# CPU.net
KiCad netlist of a schematic drawn in Altium Designer
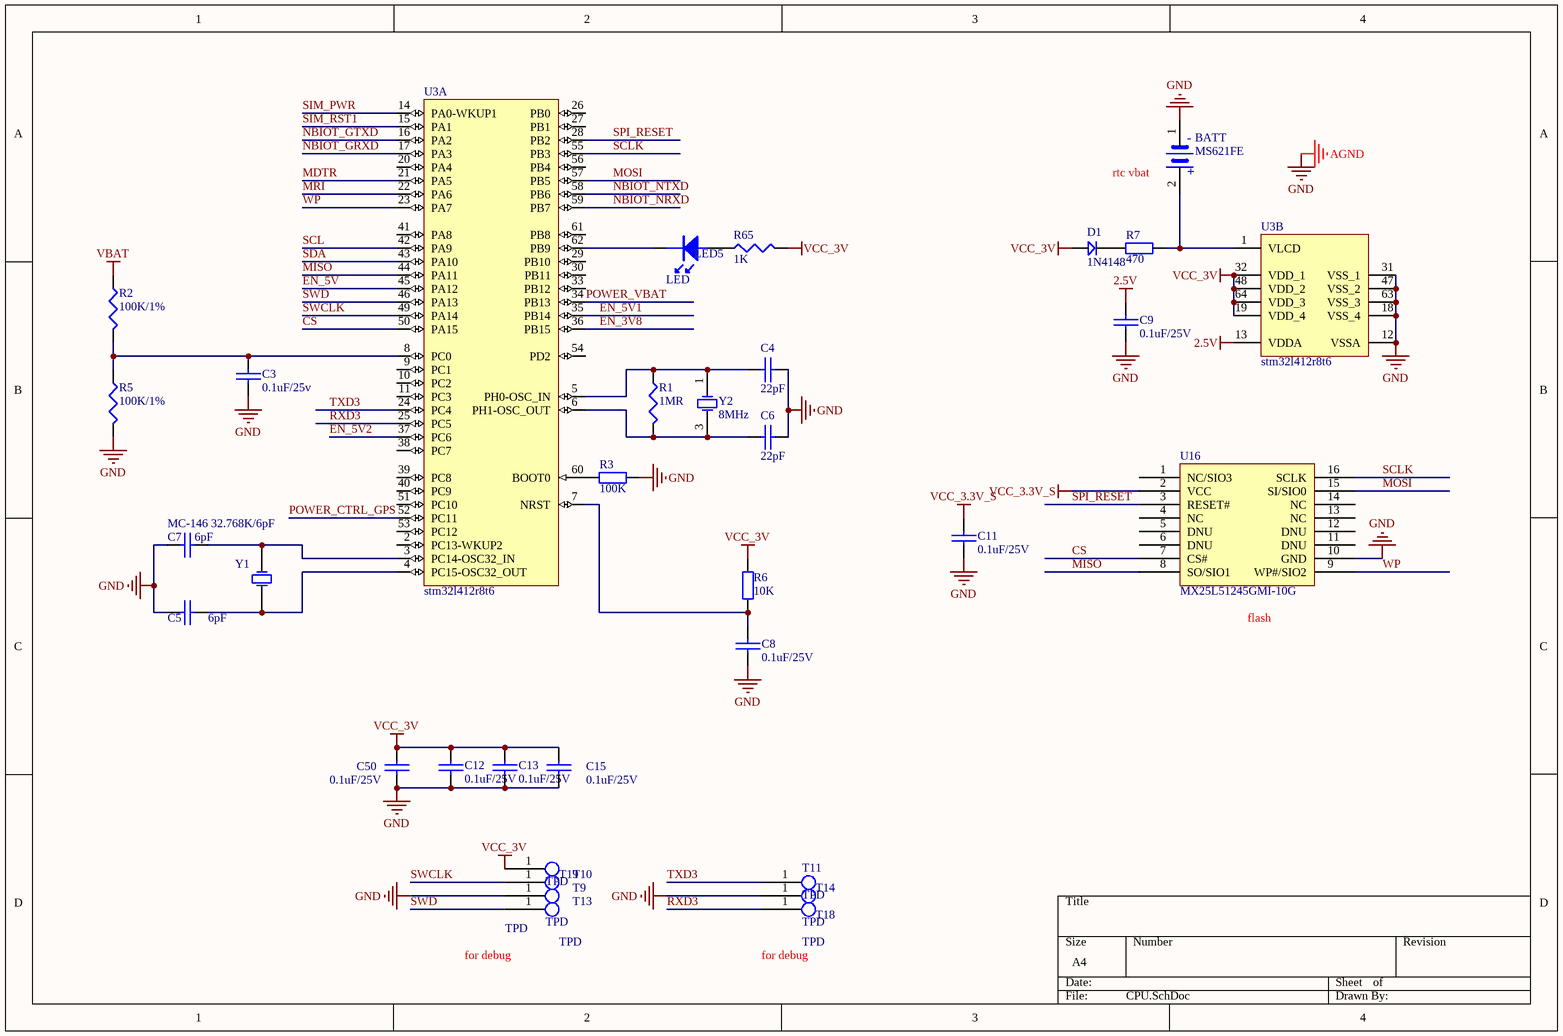
[diagram p0: CPU.SchDoc]

(export (version "E")
  (design (tool "Eeschema 10.0.6"))
  (components
    (comp (ref "BATT") (value "MS621FE") (footprint "MS621FE") (libsource (lib "Myself_1") (part "SBatery")))
    (comp (ref "C3")
      (value "0.1uF/25v")
      (footprint "0402c")
      (description "Capacitor")
      (libsource (lib "SM") (part "CAP"))
    )
    (comp (ref "C4")
      (value "22pF")
      (footprint "0402c")
      (description "Capacitor")
      (libsource (lib "SM") (part "CAP"))
    )
    (comp (ref "C5")
      (value "6pF")
      (footprint "0402c")
      (description "Capacitor")
      (libsource (lib "SM") (part "CAP"))
    )
    (comp (ref "C6")
      (value "22pF")
      (footprint "0402c")
      (description "Capacitor")
      (libsource (lib "SM") (part "CAP"))
    )
    (comp (ref "C7")
      (value "6pF")
      (footprint "0402c")
      (description "Capacitor")
      (libsource (lib "SM") (part "CAP"))
    )
    (comp (ref "C8")
      (value "0.1uF/25V")
      (footprint "0402C")
      (description "Capacitor")
      (libsource (lib "ZWLIntegrated_Library") (part "CAP"))
    )
    (comp (ref "C9")
      (value "0.1uF/25V")
      (footprint "0402C")
      (description "Capacitor")
      (libsource (lib "ZWLIntegrated_Library") (part "CAP"))
    )
    (comp (ref "C11")
      (value "0.1uF/25V")
      (footprint "0402C")
      (description "Capacitor")
      (libsource (lib "ZWLIntegrated_Library") (part "CAP"))
    )
    (comp (ref "C12")
      (value "0.1uF/25V")
      (footprint "0402C")
      (description "Capacitor")
      (libsource (lib "ZWLIntegrated_Library") (part "CAP"))
    )
    (comp (ref "C13")
      (value "0.1uF/25V")
      (footprint "0402C")
      (description "Capacitor")
      (libsource (lib "ZWLIntegrated_Library") (part "CAP"))
    )
    (comp (ref "C15")
      (value "0.1uF/25V")
      (footprint "0402C")
      (description "Capacitor")
      (libsource (lib "ZWLIntegrated_Library") (part "CAP"))
    )
    (comp (ref "C50")
      (value "0.1uF/25V")
      (footprint "0402C")
      (description "Capacitor")
      (libsource (lib "ZWLIntegrated_Library") (part "CAP"))
    )
    (comp (ref "D1")
      (value "1N4148")
      (footprint "DIODE_SOP")
      (libsource (lib "Explorer STM32F407封装库") (part "D"))
    )
    (comp (ref "LED5") (value "LED") (footprint "0603LED") (libsource (lib "我的元件库") (part "LED")))
    (comp (ref "R1")
      (value "1MR")
      (footprint "0402R")
      (description "Resistor")
      (fields (field (name "PUBLISHER") "Altium Limited"))
      (libsource (lib "SM") (part "Res3"))
    )
    (comp (ref "R2")
      (value "100K/1%")
      (footprint "0402R")
      (libsource (lib "ZWLIntegrated_Library") (part "RES1"))
    )
    (comp (ref "R3")
      (value "100K")
      (footprint "0402R")
      (description "Resistor")
      (fields (field (name "PUBLISHER") "Altium Limited"))
      (libsource (lib "Miscellaneous Devices") (part "Res2"))
    )
    (comp (ref "R5")
      (value "100K/1%")
      (footprint "0402R")
      (libsource (lib "ZWLIntegrated_Library") (part "RES1"))
    )
    (comp (ref "R6")
      (value "10K")
      (footprint "0402R")
      (description "Resistor")
      (fields (field (name "PUBLISHER") "Altium Limited"))
      (libsource (lib "") (part "Res2_1"))
    )
    (comp (ref "R7")
      (value "470")
      (footprint "0402R")
      (description "Resistor")
      (fields (field (name "PUBLISHER") "Altium Limited"))
      (libsource (lib "Miscellaneous Devices") (part "Res2"))
    )
    (comp (ref "R65")
      (value "1K")
      (footprint "0402R")
      (libsource (lib "ZWLIntegrated_Library") (part "RES1"))
    )
    (comp (ref "T9") (value "TPD") (footprint "Pcblib_20110825:TPd") (libsource (lib "stm32") (part "TPD")))
    (comp (ref "T10") (value "TPD") (footprint "Pcblib_20110825:TPd") (libsource (lib "stm32") (part "TPD")))
    (comp (ref "T11") (value "TPD") (footprint "Pcblib_20110825:TPd") (libsource (lib "stm32") (part "TPD")))
    (comp (ref "T13") (value "TPD") (footprint "Pcblib_20110825:TPd") (libsource (lib "stm32") (part "TPD")))
    (comp (ref "T14") (value "TPD") (footprint "Pcblib_20110825:TPd") (libsource (lib "stm32") (part "TPD")))
    (comp (ref "T18") (value "TPD") (footprint "Pcblib_20110825:TPd") (libsource (lib "stm32") (part "TPD")))
    (comp (ref "T19") (value "TPD") (footprint "Pcblib_20110825:TPd") (libsource (lib "stm32") (part "TPD")))
    (comp (ref "U3")
      (value "stm32l412r8t6")
      (footprint "LQFP-64")
      (fields (field (name "MANUFACTURER") "STMicroelectronics") (field (name "PARTNUMBER") "STM32L100R8T6"))
      (libsource (lib "STMicroelectronics STM32 L1") (part "STM32L100R8T6"))
    )
    (comp (ref "U16")
      (value "MX25L51245GMI-10G")
      (footprint "SOP127P1030X239-16N")
      (libsource (lib "stm32") (part "MX25L51245GMI-10G"))
    )
    (comp (ref "Y1")
      (value "MC-146 32.768K/6pF")
      (footprint "32.768K")
      (description "Crystal Oscillator")
      (fields (field (name "PUBLISHER") "Altium Limited"))
      (libsource (lib "Miscellaneous Devices") (part "XTAL"))
    )
    (comp (ref "Y2")
      (value "8MHz")
      (footprint "OSCILLATOR-3.2X2.5")
      (description "Crystal Oscillator")
      (fields (field (name "PUBLISHER") "Altium Limited"))
      (libsource (lib "") (part "XTAL_1"))
    )
  )
  (nets
    (net (code "1") (name "/CS") (class "Default")
      (node (ref "U16") (pin "7") (pinfunction "CS#_7") (pintype "passive"))
      (node (ref "U3") (pin "50") (pinfunction "PA15_50") (pintype "bidirectional"))
    )
    (net (code "2") (name "/EN_3V8") (class "Default")
      (node (ref "U3") (pin "36") (pinfunction "PB15_36") (pintype "bidirectional"))
    )
    (net (code "3") (name "/EN_5V") (class "Default")
      (node (ref "U3") (pin "45") (pinfunction "PA12_45") (pintype "bidirectional"))
    )
    (net (code "4") (name "/EN_5V1") (class "Default")
      (node (ref "U3") (pin "35") (pinfunction "PB14_35") (pintype "bidirectional"))
    )
    (net (code "5") (name "/EN_5V2") (class "Default")
      (node (ref "U3") (pin "37") (pinfunction "PC6_37") (pintype "bidirectional"))
    )
    (net (code "6") (name "/MDTR") (class "Default")
      (node (ref "U3") (pin "21") (pinfunction "PA5_21") (pintype "bidirectional"))
    )
    (net (code "7") (name "/MISO") (class "Default")
      (node (ref "U16") (pin "8") (pinfunction "SO/SIO1_8") (pintype "passive"))
      (node (ref "U3") (pin "44") (pinfunction "PA11_44") (pintype "bidirectional"))
    )
    (net (code "8") (name "/MOSI") (class "Default")
      (node (ref "U16") (pin "15") (pinfunction "SI/SIO0_15") (pintype "passive"))
      (node (ref "U3") (pin "57") (pinfunction "PB5_57") (pintype "bidirectional"))
    )
    (net (code "9") (name "/MRI") (class "Default")
      (node (ref "U3") (pin "22") (pinfunction "PA6_22") (pintype "bidirectional"))
    )
    (net (code "10") (name "/NBIOT_GRXD") (class "Default")
      (node (ref "U3") (pin "17") (pinfunction "PA3_17") (pintype "bidirectional"))
    )
    (net (code "11") (name "/NBIOT_GTXD") (class "Default")
      (node (ref "U3") (pin "16") (pinfunction "PA2_16") (pintype "bidirectional"))
    )
    (net (code "12") (name "/NBIOT_NRXD") (class "Default")
      (node (ref "U3") (pin "59") (pinfunction "PB7_59") (pintype "bidirectional"))
    )
    (net (code "13") (name "/NBIOT_NTXD") (class "Default")
      (node (ref "U3") (pin "58") (pinfunction "PB6_58") (pintype "bidirectional"))
    )
    (net (code "14") (name "/POWER_CTRL_GPS") (class "Default")
      (node (ref "U3") (pin "52") (pinfunction "PC11_52") (pintype "bidirectional"))
    )
    (net (code "15") (name "/POWER_VBAT") (class "Default")
      (node (ref "U3") (pin "34") (pinfunction "PB13_34") (pintype "bidirectional"))
    )
    (net (code "16") (name "/RXD3") (class "Default")
      (node (ref "T18") (pin "1") (pintype "passive"))
      (node (ref "U3") (pin "25") (pinfunction "PC5_25") (pintype "bidirectional"))
    )
    (net (code "17") (name "/SCL") (class "Default")
      (node (ref "U3") (pin "42") (pinfunction "PA9_42") (pintype "bidirectional"))
    )
    (net (code "18") (name "/SCLK") (class "Default")
      (node (ref "U16") (pin "16") (pinfunction "SCLK_16") (pintype "passive"))
      (node (ref "U3") (pin "55") (pinfunction "PB3_55") (pintype "bidirectional"))
    )
    (net (code "19") (name "/SDA") (class "Default")
      (node (ref "U3") (pin "43") (pinfunction "PA10_43") (pintype "bidirectional"))
    )
    (net (code "20") (name "/SIM_PWR") (class "Default")
      (node (ref "U3") (pin "14") (pinfunction "PA0-WKUP1_14") (pintype "bidirectional"))
    )
    (net (code "21") (name "/SIM_RST1") (class "Default")
      (node (ref "U3") (pin "15") (pinfunction "PA1_15") (pintype "bidirectional"))
    )
    (net (code "22") (name "/SPI_RESET") (class "Default")
      (node (ref "U16") (pin "3") (pinfunction "RESET#_3") (pintype "passive"))
      (node (ref "U3") (pin "28") (pinfunction "PB2_28") (pintype "bidirectional"))
    )
    (net (code "23") (name "/SWCLK") (class "Default")
      (node (ref "T10") (pin "1") (pintype "passive"))
      (node (ref "U3") (pin "49") (pinfunction "PA14_49") (pintype "bidirectional"))
    )
    (net (code "24") (name "/SWD") (class "Default")
      (node (ref "T9") (pin "1") (pintype "passive"))
      (node (ref "U3") (pin "46") (pinfunction "PA13_46") (pintype "bidirectional"))
    )
    (net (code "25") (name "/TXD3") (class "Default")
      (node (ref "T11") (pin "1") (pintype "passive"))
      (node (ref "U3") (pin "24") (pinfunction "PC4_24") (pintype "bidirectional"))
    )
    (net (code "26") (name "/WP") (class "Default")
      (node (ref "U16") (pin "9") (pinfunction "WP#/SIO2_9") (pintype "passive"))
      (node (ref "U3") (pin "23") (pinfunction "PA7_23") (pintype "bidirectional"))
    )
    (net (code "27") (name "2.5V") (class "Default")
      (node (ref "C9") (pin "2") (pinfunction "2_2") (pintype "passive"))
      (node (ref "U3") (pin "13") (pinfunction "VDDA_13") (pintype "power_in"))
    )
    (net (code "28") (name "AGND") (class "Default")
      (node (ref "BATT") (pin "1") (pinfunction "1_1") (pintype "passive"))
      (node (ref "C11") (pin "1") (pinfunction "1_1") (pintype "passive"))
      (node (ref "C12") (pin "1") (pinfunction "1_1") (pintype "passive"))
      (node (ref "C13") (pin "1") (pinfunction "1_1") (pintype "passive"))
      (node (ref "C15") (pin "1") (pinfunction "1_1") (pintype "passive"))
      (node (ref "C3") (pin "2") (pinfunction "2_2") (pintype "passive"))
      (node (ref "C4") (pin "1") (pinfunction "1_1") (pintype "passive"))
      (node (ref "C5") (pin "2") (pinfunction "2_2") (pintype "passive"))
      (node (ref "C50") (pin "1") (pinfunction "1_1") (pintype "passive"))
      (node (ref "C6") (pin "1") (pinfunction "1_1") (pintype "passive"))
      (node (ref "C7") (pin "2") (pinfunction "2_2") (pintype "passive"))
      (node (ref "C8") (pin "1") (pinfunction "1_1") (pintype "passive"))
      (node (ref "C9") (pin "1") (pinfunction "1_1") (pintype "passive"))
      (node (ref "R3") (pin "2") (pinfunction "2_2") (pintype "passive"))
      (node (ref "R5") (pin "2") (pinfunction "2_2") (pintype "passive"))
      (node (ref "T13") (pin "1") (pintype "passive"))
      (node (ref "T14") (pin "1") (pintype "passive"))
      (node (ref "U16") (pin "10") (pinfunction "GND_10") (pintype "passive"))
      (node (ref "U3") (pin "12") (pinfunction "VSSA_12") (pintype "power_in"))
      (node (ref "U3") (pin "18") (pinfunction "VSS_4_18") (pintype "power_in"))
      (node (ref "U3") (pin "31") (pinfunction "VSS_1_31") (pintype "power_in"))
      (node (ref "U3") (pin "47") (pinfunction "VSS_2_47") (pintype "power_in"))
      (node (ref "U3") (pin "63") (pinfunction "VSS_3_63") (pintype "power_in"))
    )
    (net (code "29") (name "Net-(D1-Pad2)") (class "Default")
      (node (ref "D1") (pin "2") (pintype "passive"))
      (node (ref "R7") (pin "1") (pinfunction "1_1") (pintype "passive"))
    )
    (net (code "30") (name "Net-(LED5-Pad1)") (class "Default")
      (node (ref "LED5") (pin "1") (pinfunction "1_1") (pintype "passive"))
      (node (ref "R65") (pin "1") (pinfunction "1_1") (pintype "passive"))
    )
    (net (code "31") (name "Net-(U3A-BOOT0)") (class "Default")
      (node (ref "R3") (pin "1") (pinfunction "1_1") (pintype "passive"))
      (node (ref "U3") (pin "60") (pinfunction "BOOT0_60") (pintype "input"))
    )
    (net (code "32") (name "Net-(U3A-NRST)") (class "Default")
      (node (ref "C8") (pin "2") (pinfunction "2_2") (pintype "passive"))
      (node (ref "R6") (pin "2") (pinfunction "2_2") (pintype "passive"))
      (node (ref "U3") (pin "7") (pinfunction "NRST_7") (pintype "bidirectional"))
    )
    (net (code "33") (name "Net-(U3A-PB9)") (class "Default")
      (node (ref "LED5") (pin "2") (pinfunction "2_2") (pintype "passive"))
      (node (ref "U3") (pin "62") (pinfunction "PB9_62") (pintype "bidirectional"))
    )
    (net (code "34") (name "Net-(U3A-PC0)") (class "Default")
      (node (ref "C3") (pin "1") (pinfunction "1_1") (pintype "passive"))
      (node (ref "R2") (pin "2") (pinfunction "2_2") (pintype "passive"))
      (node (ref "R5") (pin "1") (pinfunction "1_1") (pintype "passive"))
      (node (ref "U3") (pin "8") (pinfunction "PC0_8") (pintype "bidirectional"))
    )
    (net (code "35") (name "Net-(U3A-PC14-OSC32_IN)") (class "Default")
      (node (ref "C7") (pin "1") (pinfunction "1_1") (pintype "passive"))
      (node (ref "U3") (pin "3") (pinfunction "PC14-OSC32_IN_3") (pintype "bidirectional"))
      (node (ref "Y1") (pin "1") (pinfunction "OSC1_1") (pintype "passive"))
    )
    (net (code "36") (name "Net-(U3A-PC15-OSC32_OUT)") (class "Default")
      (node (ref "C5") (pin "1") (pinfunction "1_1") (pintype "passive"))
      (node (ref "U3") (pin "4") (pinfunction "PC15-OSC32_OUT_4") (pintype "bidirectional"))
      (node (ref "Y1") (pin "2") (pinfunction "OSC2_2") (pintype "passive"))
    )
    (net (code "37") (name "Net-(U3A-PH0-OSC_IN)") (class "Default")
      (node (ref "C4") (pin "2") (pinfunction "2_2") (pintype "passive"))
      (node (ref "R1") (pin "1") (pinfunction "1_1") (pintype "passive"))
      (node (ref "U3") (pin "5") (pinfunction "PH0-OSC_IN_5") (pintype "bidirectional"))
      (node (ref "Y2") (pin "1") (pinfunction "OSC1_1") (pintype "passive"))
    )
    (net (code "38") (name "Net-(U3A-PH1-OSC_OUT)") (class "Default")
      (node (ref "C6") (pin "2") (pinfunction "2_2") (pintype "passive"))
      (node (ref "R1") (pin "2") (pinfunction "2_2") (pintype "passive"))
      (node (ref "U3") (pin "6") (pinfunction "PH1-OSC_OUT_6") (pintype "bidirectional"))
      (node (ref "Y2") (pin "3") (pinfunction "OSC2_3") (pintype "passive"))
    )
    (net (code "39") (name "Net-(U3B-VLCD)") (class "Default")
      (node (ref "BATT") (pin "2") (pinfunction "2_2") (pintype "passive"))
      (node (ref "R7") (pin "2") (pinfunction "2_2") (pintype "passive"))
      (node (ref "U3") (pin "1") (pinfunction "VLCD_1") (pintype "power_in"))
    )
    (net (code "40") (name "VBAT") (class "Default")
      (node (ref "R2") (pin "1") (pinfunction "1_1") (pintype "passive"))
    )
    (net (code "41") (name "VCC_3.3V_S") (class "Default")
      (node (ref "C11") (pin "2") (pinfunction "2_2") (pintype "passive"))
      (node (ref "U16") (pin "2") (pinfunction "VCC_2") (pintype "passive"))
    )
    (net (code "42") (name "VCC_3V") (class "Default")
      (node (ref "C12") (pin "2") (pinfunction "2_2") (pintype "passive"))
      (node (ref "C13") (pin "2") (pinfunction "2_2") (pintype "passive"))
      (node (ref "C15") (pin "2") (pinfunction "2_2") (pintype "passive"))
      (node (ref "C50") (pin "2") (pinfunction "2_2") (pintype "passive"))
      (node (ref "D1") (pin "1") (pintype "passive"))
      (node (ref "R6") (pin "1") (pinfunction "1_1") (pintype "passive"))
      (node (ref "R65") (pin "2") (pinfunction "2_2") (pintype "passive"))
      (node (ref "T19") (pin "1") (pintype "passive"))
      (node (ref "U3") (pin "19") (pinfunction "VDD_4_19") (pintype "power_in"))
      (node (ref "U3") (pin "32") (pinfunction "VDD_1_32") (pintype "power_in"))
      (node (ref "U3") (pin "48") (pinfunction "VDD_2_48") (pintype "power_in"))
      (node (ref "U3") (pin "64") (pinfunction "VDD_3_64") (pintype "power_in"))
    )
    (net (code "43") (name "unconnected-(U3A-PA4-Pad20)") (class "Default")
      (node (ref "U3") (pin "20") (pinfunction "PA4_20") (pintype "bidirectional"))
    )
    (net (code "44") (name "unconnected-(U3A-PA8-Pad41)") (class "Default")
      (node (ref "U3") (pin "41") (pinfunction "PA8_41") (pintype "bidirectional"))
    )
    (net (code "45") (name "unconnected-(U3A-PB0-Pad26)") (class "Default")
      (node (ref "U3") (pin "26") (pinfunction "PB0_26") (pintype "bidirectional"))
    )
    (net (code "46") (name "unconnected-(U3A-PB1-Pad27)") (class "Default")
      (node (ref "U3") (pin "27") (pinfunction "PB1_27") (pintype "bidirectional"))
    )
    (net (code "47") (name "unconnected-(U3A-PB4-Pad56)") (class "Default")
      (node (ref "U3") (pin "56") (pinfunction "PB4_56") (pintype "bidirectional"))
    )
    (net (code "48") (name "unconnected-(U3A-PB8-Pad61)") (class "Default")
      (node (ref "U3") (pin "61") (pinfunction "PB8_61") (pintype "bidirectional"))
    )
    (net (code "49") (name "unconnected-(U3A-PB10-Pad29)") (class "Default")
      (node (ref "U3") (pin "29") (pinfunction "PB10_29") (pintype "bidirectional"))
    )
    (net (code "50") (name "unconnected-(U3A-PB11-Pad30)") (class "Default")
      (node (ref "U3") (pin "30") (pinfunction "PB11_30") (pintype "bidirectional"))
    )
    (net (code "51") (name "unconnected-(U3A-PB12-Pad33)") (class "Default")
      (node (ref "U3") (pin "33") (pinfunction "PB12_33") (pintype "bidirectional"))
    )
    (net (code "52") (name "unconnected-(U3A-PC1-Pad9)") (class "Default")
      (node (ref "U3") (pin "9") (pinfunction "PC1_9") (pintype "bidirectional"))
    )
    (net (code "53") (name "unconnected-(U3A-PC2-Pad10)") (class "Default")
      (node (ref "U3") (pin "10") (pinfunction "PC2_10") (pintype "bidirectional"))
    )
    (net (code "54") (name "unconnected-(U3A-PC3-Pad11)") (class "Default")
      (node (ref "U3") (pin "11") (pinfunction "PC3_11") (pintype "bidirectional"))
    )
    (net (code "55") (name "unconnected-(U3A-PC7-Pad38)") (class "Default")
      (node (ref "U3") (pin "38") (pinfunction "PC7_38") (pintype "bidirectional"))
    )
    (net (code "56") (name "unconnected-(U3A-PC8-Pad39)") (class "Default")
      (node (ref "U3") (pin "39") (pinfunction "PC8_39") (pintype "bidirectional"))
    )
    (net (code "57") (name "unconnected-(U3A-PC9-Pad40)") (class "Default")
      (node (ref "U3") (pin "40") (pinfunction "PC9_40") (pintype "bidirectional"))
    )
    (net (code "58") (name "unconnected-(U3A-PC10-Pad51)") (class "Default")
      (node (ref "U3") (pin "51") (pinfunction "PC10_51") (pintype "bidirectional"))
    )
    (net (code "59") (name "unconnected-(U3A-PC12-Pad53)") (class "Default")
      (node (ref "U3") (pin "53") (pinfunction "PC12_53") (pintype "bidirectional"))
    )
    (net (code "60") (name "unconnected-(U3A-PC13-WKUP2-Pad2)") (class "Default")
      (node (ref "U3") (pin "2") (pinfunction "PC13-WKUP2_2") (pintype "bidirectional"))
    )
    (net (code "61") (name "unconnected-(U3A-PD2-Pad54)") (class "Default")
      (node (ref "U3") (pin "54") (pinfunction "PD2_54") (pintype "bidirectional"))
    )
    (net (code "62") (name "unconnected-(U16-DNU-Pad5)") (class "Default")
      (node (ref "U16") (pin "5") (pinfunction "DNU_5") (pintype "passive"))
    )
    (net (code "63") (name "unconnected-(U16-DNU-Pad6)") (class "Default")
      (node (ref "U16") (pin "6") (pinfunction "DNU_6") (pintype "passive"))
    )
    (net (code "64") (name "unconnected-(U16-DNU-Pad11)") (class "Default")
      (node (ref "U16") (pin "11") (pinfunction "DNU_11") (pintype "passive"))
    )
    (net (code "65") (name "unconnected-(U16-DNU-Pad12)") (class "Default")
      (node (ref "U16") (pin "12") (pinfunction "DNU_12") (pintype "passive"))
    )
    (net (code "66") (name "unconnected-(U16-NC-Pad4)") (class "Default")
      (node (ref "U16") (pin "4") (pinfunction "NC_4") (pintype "passive"))
    )
    (net (code "67") (name "unconnected-(U16-NC-Pad13)") (class "Default")
      (node (ref "U16") (pin "13") (pinfunction "NC_13") (pintype "passive"))
    )
    (net (code "68") (name "unconnected-(U16-NC-Pad14)") (class "Default")
      (node (ref "U16") (pin "14") (pinfunction "NC_14") (pintype "passive"))
    )
    (net (code "69") (name "unconnected-(U16-NC{slash}SIO3-Pad1)") (class "Default")
      (node (ref "U16") (pin "1") (pinfunction "NC/SIO3_1") (pintype "passive"))
    )
  )
)
